# SCH_ACSI2STM_EasyEDA.net
KiCad netlist of a schematic drawn in EasyEDA
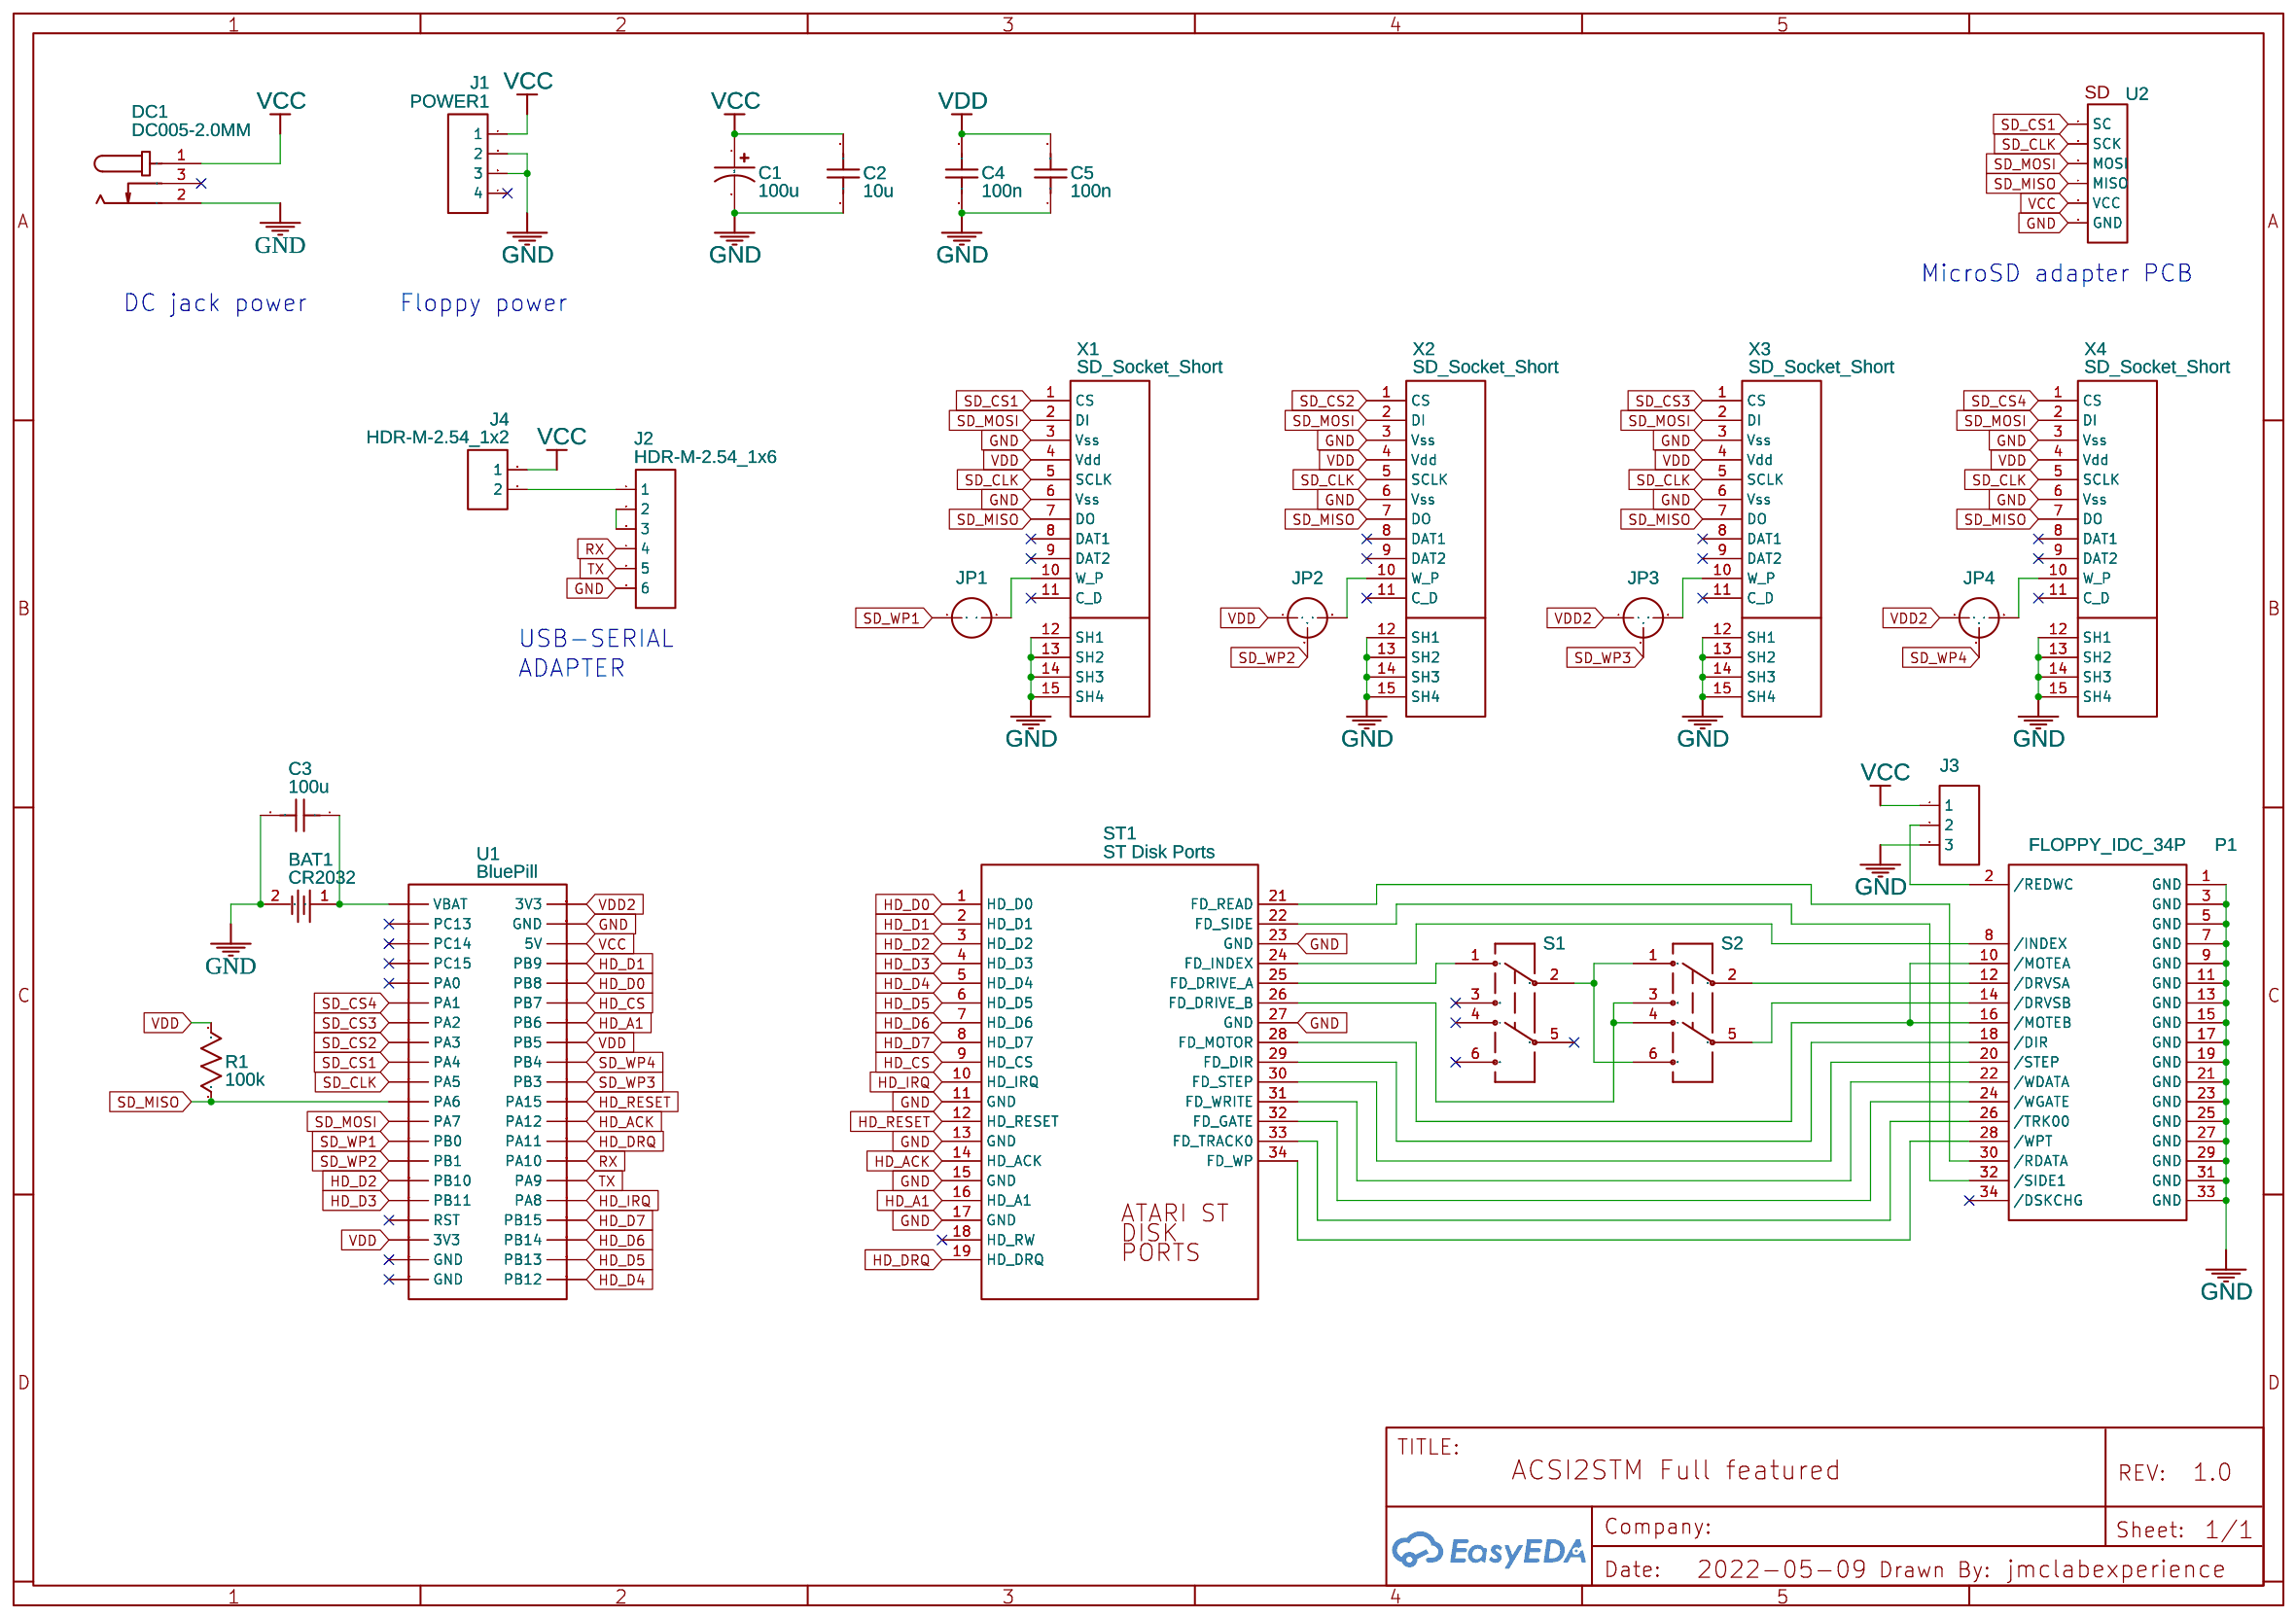
[diagram p0: schematic sheet]

(export (version "E")
  (design (tool "Eeschema 10.0.6"))
  (components
    (comp (ref "BAT1")
      (value "CR2032")
      (fields (field (name "BOM_Supplier Part") "C9900007674"))
      (libsource (lib "") (part "CR2032_C9900007674"))
    )
    (comp (ref "C1") (value "100u") (libsource (lib "") (part "CE_TH_D6.3×F2.5_US")))
    (comp (ref "C2") (value "10u") (libsource (lib "") (part "C_1206_US_1")))
    (comp (ref "C3") (value "100u") (libsource (lib "") (part "C_1206_US")))
    (comp (ref "C4") (value "100n") (libsource (lib "") (part "C_0805_US")))
    (comp (ref "C5") (value "100n") (libsource (lib "") (part "C_0805_US")))
    (comp (ref "DC1")
      (value "DC005-2.0MM")
      (fields (field (name "BOM_Supplier Part") "C111567"))
      (libsource (lib "") (part "DC005-2.0MM"))
    )
    (comp (ref "J1")
      (value "POWER1")
      (fields (field (name "BOM_Supplier Part") "C124378"))
      (libsource (lib "") (part "HDR-M-2.54_1x4"))
    )
    (comp (ref "J2")
      (value "HDR-M-2.54_1x6")
      (fields (field (name "BOM_Supplier Part") "C190819"))
      (libsource (lib "") (part "HDR-M-2.54_1x6"))
    )
    (comp (ref "J3")
      (value "HDR-M-2.54_1x3")
      (fields (field (name "BOM_Supplier Part") "C180248"))
      (libsource (lib "") (part "HDR-M-2.54_1x3"))
    )
    (comp (ref "J4")
      (value "HDR-M-2.54_1x2")
      (fields (field (name "BOM_Supplier Part") "C124375"))
      (libsource (lib "") (part "HDR-M-2.54_1x2"))
    )
    (comp (ref "JP1") (value "Solder jumper 2P") (libsource (lib "") (part "Solder jumper 2P")))
    (comp (ref "JP2") (value "Solder jumper 3P") (libsource (lib "") (part "Solder jumper 3P")))
    (comp (ref "JP3") (value "Solder jumper 3P") (libsource (lib "") (part "Solder jumper 3P")))
    (comp (ref "JP4") (value "Solder jumper 3P") (libsource (lib "") (part "Solder jumper 3P")))
    (comp (ref "P1")
      (value "FLOPPY_IDC_34P")
      (fields
        (field (name "BOM_Manufacturer Part") "Z-231011034106")
        (field (name "BOM_Supplier Part") "c221055")
      )
      (libsource (lib "") (part "FLOPPY_IDC_34P"))
    )
    (comp (ref "R1") (value "100k") (libsource (lib "") (part "R_0805_US")))
    (comp (ref "S1") (value "SWITCH-DPDT") (libsource (lib "") (part "SWITCH-DPDT")))
    (comp (ref "S2") (value "SWITCH-DPDT") (libsource (lib "") (part "SWITCH-DPDT")))
    (comp (ref "ST1") (value "ST Disk Ports") (libsource (lib "") (part "ST Disk Ports")))
    (comp (ref "U1") (value "BluePill") (libsource (lib "") (part "BluePill")))
    (comp (ref "U2") (value "SD1") (libsource (lib "") (part "SD")))
    (comp (ref "X1") (value "SD_Socket_Short") (libsource (lib "") (part "SD_Socket_Short")))
    (comp (ref "X2") (value "SD_Socket_Short") (libsource (lib "") (part "SD_Socket_Short")))
    (comp (ref "X3") (value "SD_Socket_Short") (libsource (lib "") (part "SD_Socket_Short")))
    (comp (ref "X4") (value "SD_Socket_Short") (libsource (lib "") (part "SD_Socket_Short")))
  )
  (nets
    (net (code "1") (name "GND") (class "Default")
      (node (ref "BAT1") (pin "2") (pinfunction "2_2") (pintype "input"))
      (node (ref "C1") (pin "2") (pinfunction "2_2") (pintype "unspecified"))
      (node (ref "C2") (pin "1") (pinfunction "1_1") (pintype "unspecified"))
      (node (ref "C3") (pin "2") (pinfunction "2_2") (pintype "unspecified"))
      (node (ref "C4") (pin "1") (pinfunction "1_1") (pintype "unspecified"))
      (node (ref "C5") (pin "1") (pinfunction "1_1") (pintype "unspecified"))
      (node (ref "DC1") (pin "2") (pinfunction "2_2") (pintype "unspecified"))
      (node (ref "J1") (pin "2") (pinfunction "2_2") (pintype "unspecified"))
      (node (ref "J1") (pin "3") (pinfunction "3_3") (pintype "unspecified"))
      (node (ref "J2") (pin "6") (pinfunction "6_6") (pintype "input"))
      (node (ref "J3") (pin "3") (pinfunction "3_3") (pintype "input"))
      (node (ref "P1") (pin "1") (pinfunction "GND_1") (pintype "unspecified"))
      (node (ref "P1") (pin "11") (pinfunction "GND_11") (pintype "unspecified"))
      (node (ref "P1") (pin "13") (pinfunction "GND_13") (pintype "unspecified"))
      (node (ref "P1") (pin "15") (pinfunction "GND_15") (pintype "unspecified"))
      (node (ref "P1") (pin "17") (pinfunction "GND_17") (pintype "unspecified"))
      (node (ref "P1") (pin "19") (pinfunction "GND_19") (pintype "unspecified"))
      (node (ref "P1") (pin "21") (pinfunction "GND_21") (pintype "unspecified"))
      (node (ref "P1") (pin "23") (pinfunction "GND_23") (pintype "unspecified"))
      (node (ref "P1") (pin "25") (pinfunction "GND_25") (pintype "unspecified"))
      (node (ref "P1") (pin "27") (pinfunction "GND_27") (pintype "unspecified"))
      (node (ref "P1") (pin "29") (pinfunction "GND_29") (pintype "unspecified"))
      (node (ref "P1") (pin "3") (pinfunction "GND_3") (pintype "unspecified"))
      (node (ref "P1") (pin "31") (pinfunction "GND_31") (pintype "unspecified"))
      (node (ref "P1") (pin "33") (pinfunction "GND_33") (pintype "unspecified"))
      (node (ref "P1") (pin "5") (pinfunction "GND_5") (pintype "unspecified"))
      (node (ref "P1") (pin "7") (pinfunction "GND_7") (pintype "unspecified"))
      (node (ref "P1") (pin "9") (pinfunction "GND_9") (pintype "unspecified"))
      (node (ref "ST1") (pin "11") (pinfunction "GND_11") (pintype "unspecified"))
      (node (ref "ST1") (pin "13") (pinfunction "GND_13") (pintype "unspecified"))
      (node (ref "ST1") (pin "15") (pinfunction "GND_15") (pintype "unspecified"))
      (node (ref "ST1") (pin "17") (pinfunction "GND_17") (pintype "unspecified"))
      (node (ref "ST1") (pin "23") (pinfunction "GND_23") (pintype "unspecified"))
      (node (ref "ST1") (pin "27") (pinfunction "GND_27") (pintype "unspecified"))
      (node (ref "U1") (pin "GND_3") (pinfunction "GND_GND_3") (pintype "unspecified"))
      (node (ref "U2") (pin "6") (pinfunction "GND_6") (pintype "input"))
      (node (ref "X1") (pin "12") (pinfunction "SH1_12") (pintype "unspecified"))
      (node (ref "X1") (pin "13") (pinfunction "SH2_13") (pintype "unspecified"))
      (node (ref "X1") (pin "14") (pinfunction "SH3_14") (pintype "unspecified"))
      (node (ref "X1") (pin "15") (pinfunction "SH4_15") (pintype "unspecified"))
      (node (ref "X1") (pin "3") (pinfunction "Vss_3") (pintype "unspecified"))
      (node (ref "X1") (pin "6") (pinfunction "Vss_6") (pintype "unspecified"))
      (node (ref "X2") (pin "12") (pinfunction "SH1_12") (pintype "unspecified"))
      (node (ref "X2") (pin "13") (pinfunction "SH2_13") (pintype "unspecified"))
      (node (ref "X2") (pin "14") (pinfunction "SH3_14") (pintype "unspecified"))
      (node (ref "X2") (pin "15") (pinfunction "SH4_15") (pintype "unspecified"))
      (node (ref "X2") (pin "3") (pinfunction "Vss_3") (pintype "unspecified"))
      (node (ref "X2") (pin "6") (pinfunction "Vss_6") (pintype "unspecified"))
      (node (ref "X3") (pin "12") (pinfunction "SH1_12") (pintype "unspecified"))
      (node (ref "X3") (pin "13") (pinfunction "SH2_13") (pintype "unspecified"))
      (node (ref "X3") (pin "14") (pinfunction "SH3_14") (pintype "unspecified"))
      (node (ref "X3") (pin "15") (pinfunction "SH4_15") (pintype "unspecified"))
      (node (ref "X3") (pin "3") (pinfunction "Vss_3") (pintype "unspecified"))
      (node (ref "X3") (pin "6") (pinfunction "Vss_6") (pintype "unspecified"))
      (node (ref "X4") (pin "12") (pinfunction "SH1_12") (pintype "unspecified"))
      (node (ref "X4") (pin "13") (pinfunction "SH2_13") (pintype "unspecified"))
      (node (ref "X4") (pin "14") (pinfunction "SH3_14") (pintype "unspecified"))
      (node (ref "X4") (pin "15") (pinfunction "SH4_15") (pintype "unspecified"))
      (node (ref "X4") (pin "3") (pinfunction "Vss_3") (pintype "unspecified"))
      (node (ref "X4") (pin "6") (pinfunction "Vss_6") (pintype "unspecified"))
    )
    (net (code "2") (name "HD_A1") (class "Default")
      (node (ref "ST1") (pin "16") (pinfunction "HD_A1_16") (pintype "unspecified"))
      (node (ref "U1") (pin "PB6") (pinfunction "PB6_PB6") (pintype "unspecified"))
    )
    (net (code "3") (name "HD_ACK") (class "Default")
      (node (ref "ST1") (pin "14") (pinfunction "HD_ACK_14") (pintype "unspecified"))
      (node (ref "U1") (pin "PA12") (pinfunction "PA12_PA12") (pintype "unspecified"))
    )
    (net (code "4") (name "HD_CS") (class "Default")
      (node (ref "ST1") (pin "9") (pinfunction "HD_CS_9") (pintype "unspecified"))
      (node (ref "U1") (pin "PB7") (pinfunction "PB7_PB7") (pintype "unspecified"))
    )
    (net (code "5") (name "HD_D0") (class "Default")
      (node (ref "ST1") (pin "1") (pinfunction "HD_D0_1") (pintype "unspecified"))
      (node (ref "U1") (pin "PB8") (pinfunction "PB8_PB8") (pintype "unspecified"))
    )
    (net (code "6") (name "HD_D1") (class "Default")
      (node (ref "ST1") (pin "2") (pinfunction "HD_D1_2") (pintype "unspecified"))
      (node (ref "U1") (pin "PB9") (pinfunction "PB9_PB9") (pintype "unspecified"))
    )
    (net (code "7") (name "HD_D2") (class "Default")
      (node (ref "ST1") (pin "3") (pinfunction "HD_D2_3") (pintype "unspecified"))
      (node (ref "U1") (pin "PB10") (pinfunction "PB10_PB10") (pintype "unspecified"))
    )
    (net (code "8") (name "HD_D3") (class "Default")
      (node (ref "ST1") (pin "4") (pinfunction "HD_D3_4") (pintype "unspecified"))
      (node (ref "U1") (pin "PB11") (pinfunction "PB11_PB11") (pintype "unspecified"))
    )
    (net (code "9") (name "HD_D4") (class "Default")
      (node (ref "ST1") (pin "5") (pinfunction "HD_D4_5") (pintype "unspecified"))
      (node (ref "U1") (pin "PB12") (pinfunction "PB12_PB12") (pintype "unspecified"))
    )
    (net (code "10") (name "HD_D5") (class "Default")
      (node (ref "ST1") (pin "6") (pinfunction "HD_D5_6") (pintype "unspecified"))
      (node (ref "U1") (pin "PB13") (pinfunction "PB13_PB13") (pintype "unspecified"))
    )
    (net (code "11") (name "HD_D6") (class "Default")
      (node (ref "ST1") (pin "7") (pinfunction "HD_D6_7") (pintype "unspecified"))
      (node (ref "U1") (pin "PB14") (pinfunction "PB14_PB14") (pintype "unspecified"))
    )
    (net (code "12") (name "HD_D7") (class "Default")
      (node (ref "ST1") (pin "8") (pinfunction "HD_D7_8") (pintype "unspecified"))
      (node (ref "U1") (pin "PB15") (pinfunction "PB15_PB15") (pintype "unspecified"))
    )
    (net (code "13") (name "HD_DRQ") (class "Default")
      (node (ref "ST1") (pin "19") (pinfunction "HD_DRQ_19") (pintype "unspecified"))
      (node (ref "U1") (pin "PA11") (pinfunction "PA11_PA11") (pintype "unspecified"))
    )
    (net (code "14") (name "HD_IRQ") (class "Default")
      (node (ref "ST1") (pin "10") (pinfunction "HD_IRQ_10") (pintype "unspecified"))
      (node (ref "U1") (pin "PA8") (pinfunction "PA8_PA8") (pintype "unspecified"))
    )
    (net (code "15") (name "HD_RESET") (class "Default")
      (node (ref "ST1") (pin "12") (pinfunction "HD_RESET_12") (pintype "unspecified"))
      (node (ref "U1") (pin "PA15") (pinfunction "PA15_PA15") (pintype "unspecified"))
    )
    (net (code "16") (name "Net-(BAT1-Pad1)") (class "Default")
      (node (ref "BAT1") (pin "1") (pinfunction "1_1") (pintype "input"))
      (node (ref "C3") (pin "1") (pinfunction "1_1") (pintype "unspecified"))
      (node (ref "U1") (pin "VBAT") (pinfunction "VBAT_VBAT") (pintype "unspecified"))
    )
    (net (code "17") (name "Net-(J2-Pad1)") (class "Default")
      (node (ref "J2") (pin "1") (pinfunction "1_1") (pintype "input"))
      (node (ref "J4") (pin "2") (pinfunction "2_2") (pintype "unspecified"))
    )
    (net (code "18") (name "Net-(J2-Pad2)") (class "Default")
      (node (ref "J2") (pin "2") (pinfunction "2_2") (pintype "input"))
      (node (ref "J2") (pin "3") (pinfunction "3_3") (pintype "input"))
    )
    (net (code "19") (name "Net-(P1-{slash}DIR)") (class "Default")
      (node (ref "P1") (pin "18") (pinfunction "/DIR_18") (pintype "unspecified"))
      (node (ref "ST1") (pin "29") (pinfunction "FD_DIR_29") (pintype "unspecified"))
    )
    (net (code "20") (name "Net-(P1-{slash}DRVSA)") (class "Default")
      (node (ref "P1") (pin "12") (pinfunction "/DRVSA_12") (pintype "unspecified"))
      (node (ref "S2") (pin "2") (pinfunction "2_2") (pintype "unspecified"))
    )
    (net (code "21") (name "Net-(P1-{slash}DRVSB)") (class "Default")
      (node (ref "P1") (pin "14") (pinfunction "/DRVSB_14") (pintype "unspecified"))
      (node (ref "S2") (pin "5") (pinfunction "5_5") (pintype "unspecified"))
    )
    (net (code "22") (name "Net-(P1-{slash}INDEX)") (class "Default")
      (node (ref "P1") (pin "8") (pinfunction "/INDEX_8") (pintype "unspecified"))
      (node (ref "ST1") (pin "24") (pinfunction "FD_INDEX_24") (pintype "unspecified"))
    )
    (net (code "23") (name "Net-(P1-{slash}MOTEA)") (class "Default")
      (node (ref "P1") (pin "10") (pinfunction "/MOTEA_10") (pintype "unspecified"))
      (node (ref "P1") (pin "16") (pinfunction "/MOTEB_16") (pintype "unspecified"))
      (node (ref "ST1") (pin "28") (pinfunction "FD_MOTOR_28") (pintype "unspecified"))
    )
    (net (code "24") (name "Net-(P1-{slash}RDATA)") (class "Default")
      (node (ref "P1") (pin "30") (pinfunction "/RDATA_30") (pintype "unspecified"))
      (node (ref "ST1") (pin "21") (pinfunction "FD_READ_21") (pintype "unspecified"))
    )
    (net (code "25") (name "Net-(P1-{slash}REDWC)") (class "Default")
      (node (ref "J3") (pin "2") (pinfunction "2_2") (pintype "input"))
      (node (ref "P1") (pin "2") (pinfunction "/REDWC_2") (pintype "unspecified"))
    )
    (net (code "26") (name "Net-(P1-{slash}SIDE1)") (class "Default")
      (node (ref "P1") (pin "32") (pinfunction "/SIDE1_32") (pintype "unspecified"))
      (node (ref "ST1") (pin "22") (pinfunction "FD_SIDE_22") (pintype "unspecified"))
    )
    (net (code "27") (name "Net-(P1-{slash}STEP)") (class "Default")
      (node (ref "P1") (pin "20") (pinfunction "/STEP_20") (pintype "unspecified"))
      (node (ref "ST1") (pin "30") (pinfunction "FD_STEP_30") (pintype "unspecified"))
    )
    (net (code "28") (name "Net-(P1-{slash}TRK00)") (class "Default")
      (node (ref "P1") (pin "26") (pinfunction "/TRK00_26") (pintype "unspecified"))
      (node (ref "ST1") (pin "33") (pinfunction "FD_TRACK0_33") (pintype "unspecified"))
    )
    (net (code "29") (name "Net-(P1-{slash}WDATA)") (class "Default")
      (node (ref "P1") (pin "22") (pinfunction "/WDATA_22") (pintype "unspecified"))
      (node (ref "ST1") (pin "31") (pinfunction "FD_WRITE_31") (pintype "unspecified"))
    )
    (net (code "30") (name "Net-(P1-{slash}WGATE)") (class "Default")
      (node (ref "P1") (pin "24") (pinfunction "/WGATE_24") (pintype "unspecified"))
      (node (ref "ST1") (pin "32") (pinfunction "FD_GATE_32") (pintype "unspecified"))
    )
    (net (code "31") (name "Net-(P1-{slash}WPT)") (class "Default")
      (node (ref "P1") (pin "28") (pinfunction "/WPT_28") (pintype "unspecified"))
      (node (ref "ST1") (pin "34") (pinfunction "FD_WP_34") (pintype "unspecified"))
    )
    (net (code "32") (name "Net-(S1-Pad2)") (class "Default")
      (node (ref "S1") (pin "2") (pinfunction "2_2") (pintype "unspecified"))
      (node (ref "S2") (pin "1") (pinfunction "1_1") (pintype "unspecified"))
      (node (ref "S2") (pin "6") (pinfunction "6_6") (pintype "unspecified"))
    )
    (net (code "33") (name "Net-(ST1-FD_DRIVE_A)") (class "Default")
      (node (ref "S1") (pin "1") (pinfunction "1_1") (pintype "unspecified"))
      (node (ref "ST1") (pin "25") (pinfunction "FD_DRIVE_A_25") (pintype "unspecified"))
    )
    (net (code "34") (name "Net-(ST1-FD_DRIVE_B)") (class "Default")
      (node (ref "S2") (pin "3") (pinfunction "3_3") (pintype "unspecified"))
      (node (ref "S2") (pin "4") (pinfunction "4_4") (pintype "unspecified"))
      (node (ref "ST1") (pin "26") (pinfunction "FD_DRIVE_B_26") (pintype "unspecified"))
    )
    (net (code "35") (name "Net-(X1-W_P)") (class "Default")
      (node (ref "JP1") (pin "2") (pinfunction "2_2") (pintype "unspecified"))
      (node (ref "X1") (pin "10") (pinfunction "W_P_10") (pintype "unspecified"))
    )
    (net (code "36") (name "Net-(X2-W_P)") (class "Default")
      (node (ref "JP2") (pin "3") (pinfunction "3_3") (pintype "unspecified"))
      (node (ref "X2") (pin "10") (pinfunction "W_P_10") (pintype "unspecified"))
    )
    (net (code "37") (name "Net-(X3-W_P)") (class "Default")
      (node (ref "JP3") (pin "3") (pinfunction "3_3") (pintype "unspecified"))
      (node (ref "X3") (pin "10") (pinfunction "W_P_10") (pintype "unspecified"))
    )
    (net (code "38") (name "Net-(X4-W_P)") (class "Default")
      (node (ref "JP4") (pin "3") (pinfunction "3_3") (pintype "unspecified"))
      (node (ref "X4") (pin "10") (pinfunction "W_P_10") (pintype "unspecified"))
    )
    (net (code "39") (name "RX") (class "Default")
      (node (ref "J2") (pin "4") (pinfunction "4_4") (pintype "input"))
      (node (ref "U1") (pin "PA10") (pinfunction "PA10_PA10") (pintype "unspecified"))
    )
    (net (code "40") (name "SD_CLK") (class "Default")
      (node (ref "U1") (pin "PA5") (pinfunction "PA5_PA5") (pintype "unspecified"))
      (node (ref "U2") (pin "2") (pinfunction "SCK_2") (pintype "input"))
      (node (ref "X1") (pin "5") (pinfunction "SCLK_5") (pintype "unspecified"))
      (node (ref "X2") (pin "5") (pinfunction "SCLK_5") (pintype "unspecified"))
      (node (ref "X3") (pin "5") (pinfunction "SCLK_5") (pintype "unspecified"))
      (node (ref "X4") (pin "5") (pinfunction "SCLK_5") (pintype "unspecified"))
    )
    (net (code "41") (name "SD_CS1") (class "Default")
      (node (ref "U1") (pin "PA4") (pinfunction "PA4_PA4") (pintype "unspecified"))
      (node (ref "U2") (pin "1") (pinfunction "SC_1") (pintype "input"))
      (node (ref "X1") (pin "1") (pinfunction "CS_1") (pintype "unspecified"))
    )
    (net (code "42") (name "SD_CS2") (class "Default")
      (node (ref "U1") (pin "PA3") (pinfunction "PA3_PA3") (pintype "unspecified"))
      (node (ref "X2") (pin "1") (pinfunction "CS_1") (pintype "unspecified"))
    )
    (net (code "43") (name "SD_CS3") (class "Default")
      (node (ref "U1") (pin "PA2") (pinfunction "PA2_PA2") (pintype "unspecified"))
      (node (ref "X3") (pin "1") (pinfunction "CS_1") (pintype "unspecified"))
    )
    (net (code "44") (name "SD_CS4") (class "Default")
      (node (ref "U1") (pin "PA1") (pinfunction "PA1_PA1") (pintype "unspecified"))
      (node (ref "X4") (pin "1") (pinfunction "CS_1") (pintype "unspecified"))
    )
    (net (code "45") (name "SD_MISO") (class "Default")
      (node (ref "R1") (pin "1") (pinfunction "1_1") (pintype "unspecified"))
      (node (ref "U1") (pin "PA6") (pinfunction "PA6_PA6") (pintype "unspecified"))
      (node (ref "U2") (pin "4") (pinfunction "MISO_4") (pintype "input"))
      (node (ref "X1") (pin "7") (pinfunction "DO_7") (pintype "unspecified"))
      (node (ref "X2") (pin "7") (pinfunction "DO_7") (pintype "unspecified"))
      (node (ref "X3") (pin "7") (pinfunction "DO_7") (pintype "unspecified"))
      (node (ref "X4") (pin "7") (pinfunction "DO_7") (pintype "unspecified"))
    )
    (net (code "46") (name "SD_MOSI") (class "Default")
      (node (ref "U1") (pin "PA7") (pinfunction "PA7_PA7") (pintype "unspecified"))
      (node (ref "U2") (pin "3") (pinfunction "MOSI_3") (pintype "input"))
      (node (ref "X1") (pin "2") (pinfunction "DI_2") (pintype "unspecified"))
      (node (ref "X2") (pin "2") (pinfunction "DI_2") (pintype "unspecified"))
      (node (ref "X3") (pin "2") (pinfunction "DI_2") (pintype "unspecified"))
      (node (ref "X4") (pin "2") (pinfunction "DI_2") (pintype "unspecified"))
    )
    (net (code "47") (name "SD_WP1") (class "Default")
      (node (ref "JP1") (pin "1") (pinfunction "1_1") (pintype "unspecified"))
      (node (ref "U1") (pin "PB0") (pinfunction "PB0_PB0") (pintype "unspecified"))
    )
    (net (code "48") (name "SD_WP2") (class "Default")
      (node (ref "JP2") (pin "2") (pinfunction "2_2") (pintype "unspecified"))
      (node (ref "U1") (pin "PB1") (pinfunction "PB1_PB1") (pintype "unspecified"))
    )
    (net (code "49") (name "SD_WP3") (class "Default")
      (node (ref "JP3") (pin "2") (pinfunction "2_2") (pintype "unspecified"))
      (node (ref "U1") (pin "PB3") (pinfunction "PB3_PB3") (pintype "unspecified"))
    )
    (net (code "50") (name "SD_WP4") (class "Default")
      (node (ref "JP4") (pin "2") (pinfunction "2_2") (pintype "unspecified"))
      (node (ref "U1") (pin "PB4") (pinfunction "PB4_PB4") (pintype "unspecified"))
    )
    (net (code "51") (name "TX") (class "Default")
      (node (ref "J2") (pin "5") (pinfunction "5_5") (pintype "input"))
      (node (ref "U1") (pin "PA9") (pinfunction "PA9_PA9") (pintype "unspecified"))
    )
    (net (code "52") (name "VCC") (class "Default")
      (node (ref "C1") (pin "1") (pinfunction "1_1") (pintype "unspecified"))
      (node (ref "C2") (pin "2") (pinfunction "2_2") (pintype "unspecified"))
      (node (ref "DC1") (pin "1") (pinfunction "1_1") (pintype "unspecified"))
      (node (ref "J1") (pin "1") (pinfunction "1_1") (pintype "unspecified"))
      (node (ref "J3") (pin "1") (pinfunction "1_1") (pintype "input"))
      (node (ref "J4") (pin "1") (pinfunction "1_1") (pintype "unspecified"))
      (node (ref "U1") (pin "5V") (pinfunction "5V_5V") (pintype "unspecified"))
      (node (ref "U2") (pin "5") (pinfunction "VCC_5") (pintype "input"))
    )
    (net (code "53") (name "VDD") (class "Default")
      (node (ref "C4") (pin "2") (pinfunction "2_2") (pintype "unspecified"))
      (node (ref "C5") (pin "2") (pinfunction "2_2") (pintype "unspecified"))
      (node (ref "JP2") (pin "1") (pinfunction "1_1") (pintype "unspecified"))
      (node (ref "R1") (pin "2") (pinfunction "2_2") (pintype "unspecified"))
      (node (ref "U1") (pin "3V3_1") (pinfunction "3V3_3V3_1") (pintype "unspecified"))
      (node (ref "U1") (pin "PB5") (pinfunction "PB5_PB5") (pintype "unspecified"))
      (node (ref "X1") (pin "4") (pinfunction "Vdd_4") (pintype "unspecified"))
      (node (ref "X2") (pin "4") (pinfunction "Vdd_4") (pintype "unspecified"))
      (node (ref "X3") (pin "4") (pinfunction "Vdd_4") (pintype "unspecified"))
      (node (ref "X4") (pin "4") (pinfunction "Vdd_4") (pintype "unspecified"))
    )
    (net (code "54") (name "VDD2") (class "Default")
      (node (ref "JP3") (pin "1") (pinfunction "1_1") (pintype "unspecified"))
      (node (ref "JP4") (pin "1") (pinfunction "1_1") (pintype "unspecified"))
      (node (ref "U1") (pin "3V3_2") (pinfunction "3V3_3V3_2") (pintype "unspecified"))
    )
    (net (code "55") (name "unconnected-(DC1-Pad3)") (class "Default")
      (node (ref "DC1") (pin "3") (pinfunction "3_3") (pintype "unspecified+no_connect"))
    )
    (net (code "56") (name "unconnected-(J1-Pad4)") (class "Default")
      (node (ref "J1") (pin "4") (pinfunction "4_4") (pintype "unspecified+no_connect"))
    )
    (net (code "57") (name "unconnected-(P1-{slash}DSKCHG-Pad34)") (class "Default")
      (node (ref "P1") (pin "34") (pinfunction "/DSKCHG_34") (pintype "unspecified+no_connect"))
    )
    (net (code "58") (name "unconnected-(S1-Pad3)") (class "Default")
      (node (ref "S1") (pin "3") (pinfunction "3_3") (pintype "unspecified+no_connect"))
    )
    (net (code "59") (name "unconnected-(S1-Pad4)") (class "Default")
      (node (ref "S1") (pin "4") (pinfunction "4_4") (pintype "unspecified+no_connect"))
    )
    (net (code "60") (name "unconnected-(S1-Pad5)") (class "Default")
      (node (ref "S1") (pin "5") (pinfunction "5_5") (pintype "unspecified+no_connect"))
    )
    (net (code "61") (name "unconnected-(S1-Pad6)") (class "Default")
      (node (ref "S1") (pin "6") (pinfunction "6_6") (pintype "unspecified+no_connect"))
    )
    (net (code "62") (name "unconnected-(ST1-HD_RW-Pad18)") (class "Default")
      (node (ref "ST1") (pin "18") (pinfunction "HD_RW_18") (pintype "unspecified+no_connect"))
    )
    (net (code "63") (name "unconnected-(U1-GND-PadGND_1)") (class "Default")
      (node (ref "U1") (pin "GND_1") (pinfunction "GND_GND_1") (pintype "unspecified+no_connect"))
    )
    (net (code "64") (name "unconnected-(U1-GND-PadGND_2)") (class "Default")
      (node (ref "U1") (pin "GND_2") (pinfunction "GND_GND_2") (pintype "unspecified+no_connect"))
    )
    (net (code "65") (name "unconnected-(U1-PadPA0)") (class "Default")
      (node (ref "U1") (pin "PA0") (pinfunction "PA0_PA0") (pintype "unspecified+no_connect"))
    )
    (net (code "66") (name "unconnected-(U1-PadPC13)") (class "Default")
      (node (ref "U1") (pin "PC13") (pinfunction "PC13_PC13") (pintype "unspecified+no_connect"))
    )
    (net (code "67") (name "unconnected-(U1-PadPC14)") (class "Default")
      (node (ref "U1") (pin "PC14") (pinfunction "PC14_PC14") (pintype "unspecified+no_connect"))
    )
    (net (code "68") (name "unconnected-(U1-PadPC15)") (class "Default")
      (node (ref "U1") (pin "PC15") (pinfunction "PC15_PC15") (pintype "unspecified+no_connect"))
    )
    (net (code "69") (name "unconnected-(U1-PadRST)") (class "Default")
      (node (ref "U1") (pin "RST") (pinfunction "RST_RST") (pintype "unspecified+no_connect"))
    )
    (net (code "70") (name "unconnected-(X1-C_D-Pad11)") (class "Default")
      (node (ref "X1") (pin "11") (pinfunction "C_D_11") (pintype "unspecified+no_connect"))
    )
    (net (code "71") (name "unconnected-(X1-DAT1-Pad8)") (class "Default")
      (node (ref "X1") (pin "8") (pinfunction "DAT1_8") (pintype "unspecified+no_connect"))
    )
    (net (code "72") (name "unconnected-(X1-DAT2-Pad9)") (class "Default")
      (node (ref "X1") (pin "9") (pinfunction "DAT2_9") (pintype "unspecified+no_connect"))
    )
    (net (code "73") (name "unconnected-(X2-C_D-Pad11)") (class "Default")
      (node (ref "X2") (pin "11") (pinfunction "C_D_11") (pintype "unspecified+no_connect"))
    )
    (net (code "74") (name "unconnected-(X2-DAT1-Pad8)") (class "Default")
      (node (ref "X2") (pin "8") (pinfunction "DAT1_8") (pintype "unspecified+no_connect"))
    )
    (net (code "75") (name "unconnected-(X2-DAT2-Pad9)") (class "Default")
      (node (ref "X2") (pin "9") (pinfunction "DAT2_9") (pintype "unspecified+no_connect"))
    )
    (net (code "76") (name "unconnected-(X3-C_D-Pad11)") (class "Default")
      (node (ref "X3") (pin "11") (pinfunction "C_D_11") (pintype "unspecified+no_connect"))
    )
    (net (code "77") (name "unconnected-(X3-DAT1-Pad8)") (class "Default")
      (node (ref "X3") (pin "8") (pinfunction "DAT1_8") (pintype "unspecified+no_connect"))
    )
    (net (code "78") (name "unconnected-(X3-DAT2-Pad9)") (class "Default")
      (node (ref "X3") (pin "9") (pinfunction "DAT2_9") (pintype "unspecified+no_connect"))
    )
    (net (code "79") (name "unconnected-(X4-C_D-Pad11)") (class "Default")
      (node (ref "X4") (pin "11") (pinfunction "C_D_11") (pintype "unspecified+no_connect"))
    )
    (net (code "80") (name "unconnected-(X4-DAT1-Pad8)") (class "Default")
      (node (ref "X4") (pin "8") (pinfunction "DAT1_8") (pintype "unspecified+no_connect"))
    )
    (net (code "81") (name "unconnected-(X4-DAT2-Pad9)") (class "Default")
      (node (ref "X4") (pin "9") (pinfunction "DAT2_9") (pintype "unspecified+no_connect"))
    )
  )
)
